# Adafruit_SIM808_Breakout.net
KiCad netlist of a schematic drawn in EAGLE
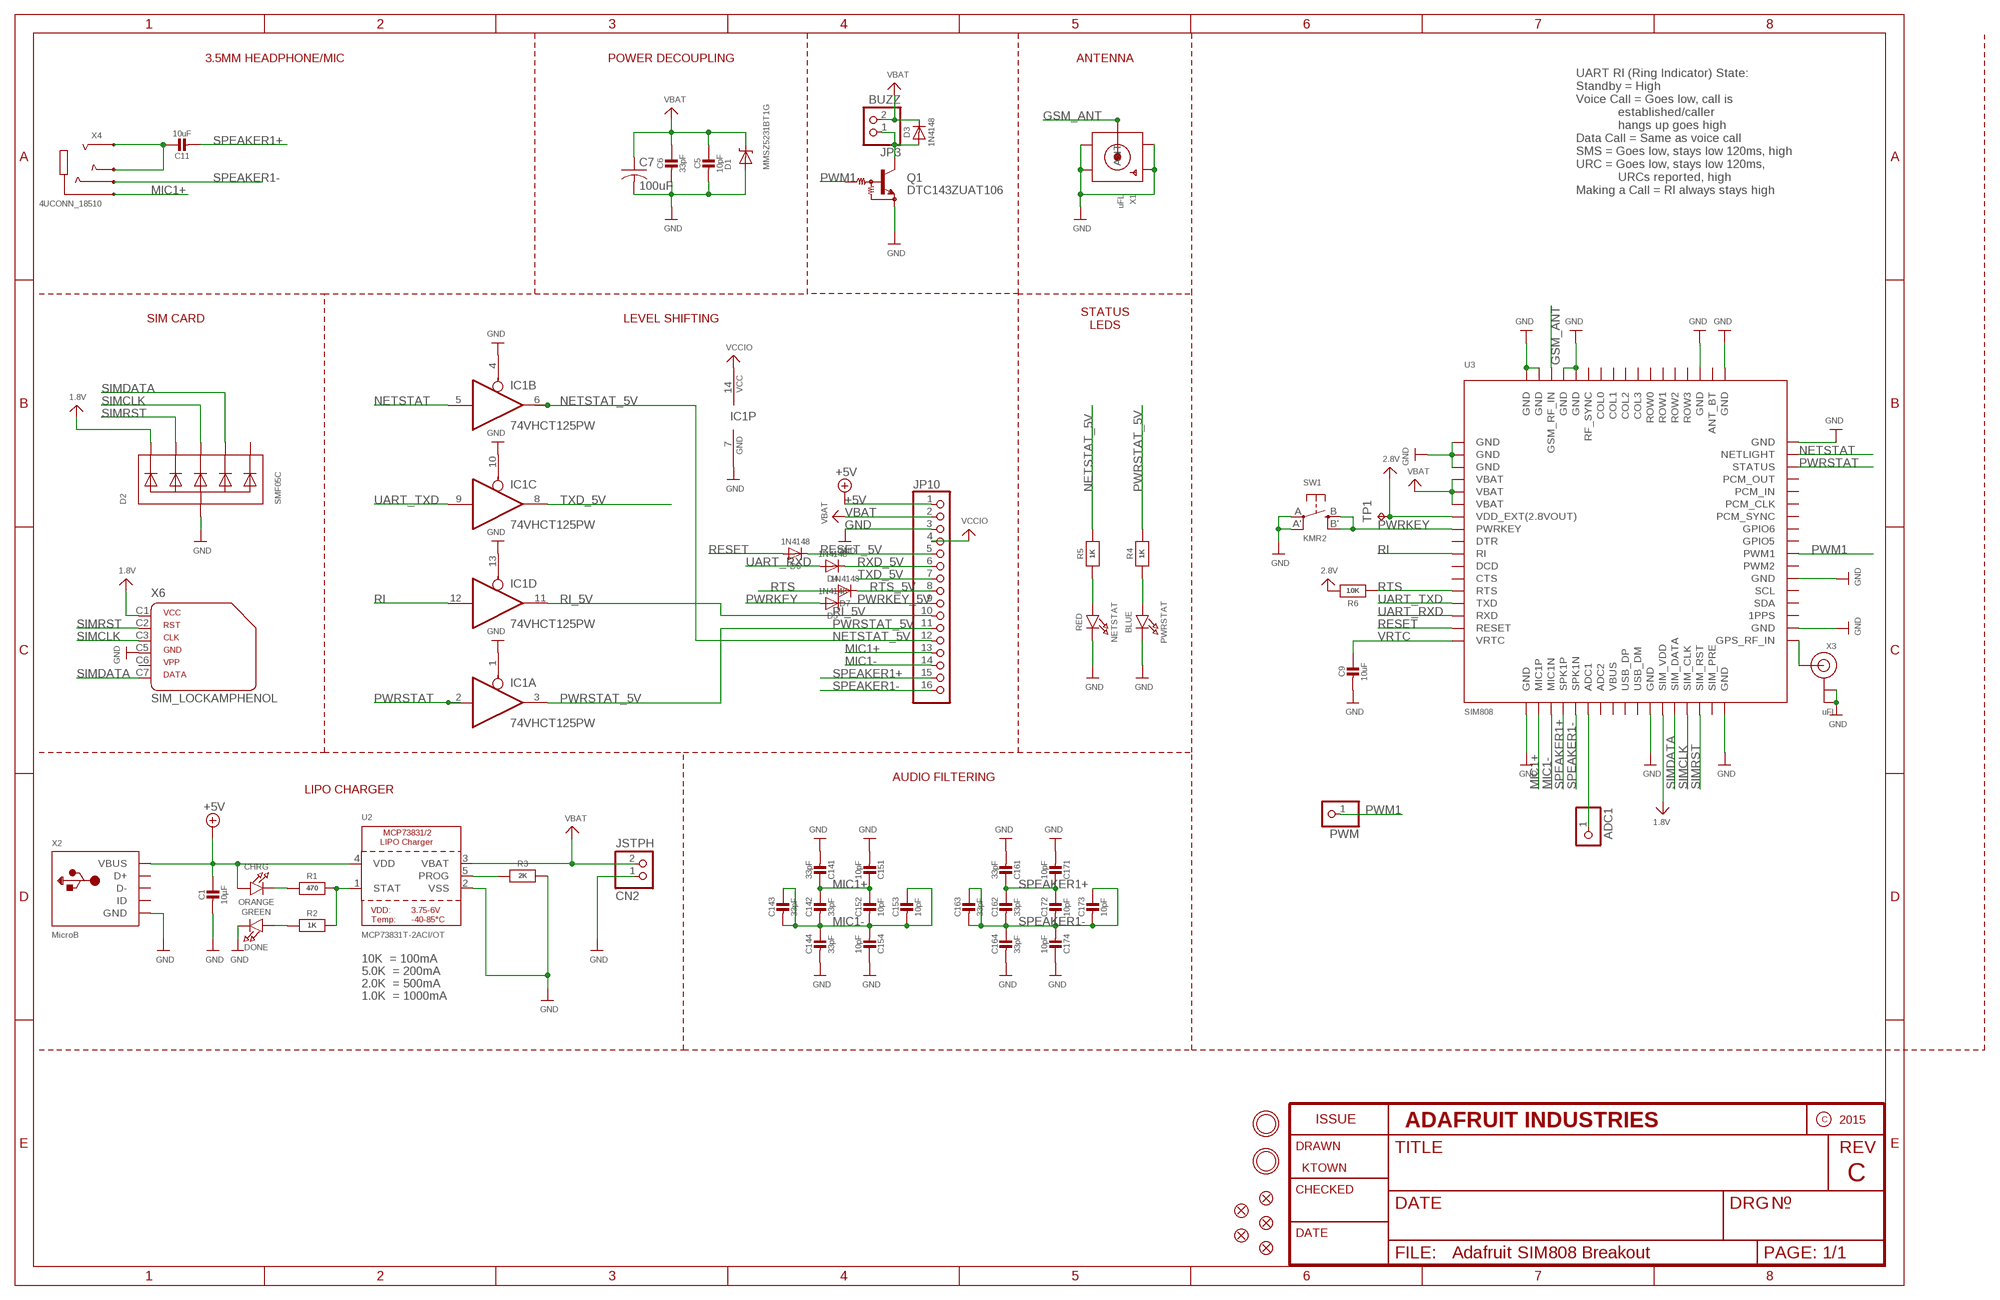
[diagram p0: schematic, sheet 1]

(export (version "E")
  (design (tool "Eeschema 10.0.6"))
  (components
    (comp (ref "ADC1")
      (value "PINHD-1X1CB")
      (footprint "eagle-import:1X01-CLEANBIG")
      (libsource (lib "eagle-import") (part "PINHD-1X1CB"))
    )
    (comp (ref "C1")
      (value "10µF")
      (footprint "eagle-import:0805-NO")
      (libsource (lib "eagle-import") (part "CAP_CERAMIC0805-NOOUTLINE"))
    )
    (comp (ref "C5")
      (value "10pF")
      (footprint "eagle-import:0805-NO")
      (libsource (lib "eagle-import") (part "CAP_CERAMIC0805-NOOUTLINE"))
    )
    (comp (ref "C6")
      (value "33pF")
      (footprint "eagle-import:0805-NO")
      (libsource (lib "eagle-import") (part "CAP_CERAMIC0805-NOOUTLINE"))
    )
    (comp (ref "C7")
      (value "100uF")
      (footprint "eagle-import:C1210")
      (libsource (lib "eagle-import") (part "C-USC1210"))
    )
    (comp (ref "C9")
      (value "10uF")
      (footprint "eagle-import:0805-NO")
      (libsource (lib "eagle-import") (part "CAP_CERAMIC0805-NOOUTLINE"))
    )
    (comp (ref "C11")
      (value "10uF")
      (footprint "eagle-import:0805-NO")
      (libsource (lib "eagle-import") (part "CAP_CERAMIC0805-NOOUTLINE"))
    )
    (comp (ref "C14")
      (value "33pF")
      (footprint "eagle-import:RESPACK_4X0603")
      (libsource (lib "eagle-import") (part "CAP_4PACK1206"))
    )
    (comp (ref "C15")
      (value "10pF")
      (footprint "eagle-import:RESPACK_4X0603")
      (libsource (lib "eagle-import") (part "CAP_4PACK1206"))
    )
    (comp (ref "C16")
      (value "33pF")
      (footprint "eagle-import:RESPACK_4X0603")
      (libsource (lib "eagle-import") (part "CAP_4PACK1206"))
    )
    (comp (ref "C17")
      (value "10pF")
      (footprint "eagle-import:RESPACK_4X0603")
      (libsource (lib "eagle-import") (part "CAP_4PACK1206"))
    )
    (comp (ref "CHRG")
      (value "ORANGE")
      (footprint "eagle-import:CHIPLED_0805_NOOUTLINE")
      (libsource (lib "eagle-import") (part "LED0805_NOOUTLINE"))
    )
    (comp (ref "CN2")
      (value "JSTPH")
      (footprint "eagle-import:JSTPH2")
      (libsource (lib "eagle-import") (part "JST_2PIN"))
    )
    (comp (ref "D1")
      (value "MMSZ5231BT1G")
      (footprint "eagle-import:SOD-123")
      (libsource (lib "eagle-import") (part "DIODE-ZENERSOD123"))
    )
    (comp (ref "D2")
      (value "SMF05C")
      (footprint "eagle-import:SOT363")
      (libsource (lib "eagle-import") (part "TVSARRAY_5LANE"))
    )
    (comp (ref "D3")
      (value "1N4148")
      (footprint "eagle-import:SOD-323")
      (libsource (lib "eagle-import") (part "DIODESOD-323"))
    )
    (comp (ref "D4")
      (value "1N4148")
      (footprint "eagle-import:SOD-323")
      (libsource (lib "eagle-import") (part "DIODESOD-323"))
    )
    (comp (ref "D5")
      (value "1N4148")
      (footprint "eagle-import:SOD-323")
      (libsource (lib "eagle-import") (part "DIODESOD-323"))
    )
    (comp (ref "D6")
      (value "1N4148")
      (footprint "eagle-import:SOD-323")
      (libsource (lib "eagle-import") (part "DIODESOD-323"))
    )
    (comp (ref "D7")
      (value "1N4148")
      (footprint "eagle-import:SOD-323")
      (libsource (lib "eagle-import") (part "DIODESOD-323"))
    )
    (comp (ref "DONE")
      (value "GREEN")
      (footprint "eagle-import:CHIPLED_0805_NOOUTLINE")
      (libsource (lib "eagle-import") (part "LED0805_NOOUTLINE"))
    )
    (comp (ref "FID1")
      (value "FIDUCIAL\"\"")
      (footprint "eagle-import:FIDUCIAL_1MM")
      (libsource (lib "eagle-import") (part "FIDUCIAL{dblquote}{dblquote}"))
    )
    (comp (ref "FID2")
      (value "FIDUCIAL\"\"")
      (footprint "eagle-import:FIDUCIAL_1MM")
      (libsource (lib "eagle-import") (part "FIDUCIAL{dblquote}{dblquote}"))
    )
    (comp (ref "FID3")
      (value "FIDUCIAL\"\"")
      (footprint "eagle-import:FIDUCIAL_1MM")
      (libsource (lib "eagle-import") (part "FIDUCIAL{dblquote}{dblquote}"))
    )
    (comp (ref "FID4")
      (value "FIDUCIAL\"\"")
      (footprint "eagle-import:FIDUCIAL_1MM")
      (libsource (lib "eagle-import") (part "FIDUCIAL{dblquote}{dblquote}"))
    )
    (comp (ref "FID5")
      (value "FIDUCIAL\"\"")
      (footprint "eagle-import:FIDUCIAL_1MM")
      (libsource (lib "eagle-import") (part "FIDUCIAL{dblquote}{dblquote}"))
    )
    (comp (ref "IC1")
      (value "74VHCT125PW")
      (footprint "eagle-import:TSSOP14")
      (libsource (lib "eagle-import") (part "74125PWABT"))
    )
    (comp (ref "JP3")
      (value "BUZZ")
      (footprint "eagle-import:1X02_ROUND")
      (libsource (lib "eagle-import") (part "HEADER-1X2ROUND"))
    )
    (comp (ref "JP10")
      (value "HEADER-1X16ROUND")
      (footprint "eagle-import:1X16_ROUND")
      (libsource (lib "eagle-import") (part "HEADER-1X16ROUND"))
    )
    (comp (ref "NETSTAT")
      (value "RED")
      (footprint "eagle-import:CHIPLED_0805_NOOUTLINE")
      (libsource (lib "eagle-import") (part "LED0805_NOOUTLINE"))
    )
    (comp (ref "PWM")
      (value "PINHD-1X1CB")
      (footprint "eagle-import:1X01-CLEANBIG")
      (libsource (lib "eagle-import") (part "PINHD-1X1CB"))
    )
    (comp (ref "PWRSTAT")
      (value "BLUE")
      (footprint "eagle-import:CHIPLED_0805_NOOUTLINE")
      (libsource (lib "eagle-import") (part "LED0805_NOOUTLINE"))
    )
    (comp (ref "Q1")
      (value "DTC143ZUAT106")
      (footprint "eagle-import:SC59-BEC")
      (libsource (lib "eagle-import") (part "-NPN_DRIVER-SC59-BECMUN2211T1"))
    )
    (comp (ref "R1")
      (value "470")
      (footprint "eagle-import:0805-NO")
      (libsource (lib "eagle-import") (part "RESISTOR0805_NOOUTLINE"))
    )
    (comp (ref "R2")
      (value "1K")
      (footprint "eagle-import:0805-NO")
      (libsource (lib "eagle-import") (part "RESISTOR0805_NOOUTLINE"))
    )
    (comp (ref "R3")
      (value "2K")
      (footprint "eagle-import:0805-NO")
      (libsource (lib "eagle-import") (part "RESISTOR0805_NOOUTLINE"))
    )
    (comp (ref "R4")
      (value "1K")
      (footprint "eagle-import:0805-NO")
      (libsource (lib "eagle-import") (part "RESISTOR0805_NOOUTLINE"))
    )
    (comp (ref "R5")
      (value "1K")
      (footprint "eagle-import:0805-NO")
      (libsource (lib "eagle-import") (part "RESISTOR0805_NOOUTLINE"))
    )
    (comp (ref "R6")
      (value "10K")
      (footprint "eagle-import:0805-NO")
      (libsource (lib "eagle-import") (part "RESISTOR0805_NOOUTLINE"))
    )
    (comp (ref "SW1")
      (value "KMR2")
      (footprint "eagle-import:BTN_KMR2_4.6X2.8")
      (libsource (lib "eagle-import") (part "SWITCH_TACT_SMT4.6X2.8"))
    )
    (comp (ref "TP1")
      (value "TPTP11R")
      (footprint "eagle-import:TP11R")
      (libsource (lib "eagle-import") (part "TPTP11R"))
    )
    (comp (ref "U$33")
      (value "MOUNTINGHOLE2.5")
      (footprint "eagle-import:MOUNTINGHOLE_2.5_PLATED")
      (libsource (lib "eagle-import") (part "MOUNTINGHOLE2.5"))
    )
    (comp (ref "U$34")
      (value "MOUNTINGHOLE2.5")
      (footprint "eagle-import:MOUNTINGHOLE_2.5_PLATED")
      (libsource (lib "eagle-import") (part "MOUNTINGHOLE2.5"))
    )
    (comp (ref "U2")
      (value "MCP73831T-2ACI/OT")
      (footprint "eagle-import:SOT23-5")
      (libsource (lib "eagle-import") (part "MCP73831/2"))
    )
    (comp (ref "U3")
      (value "SIM808")
      (footprint "eagle-import:SIM900_SMT")
      (libsource (lib "eagle-import") (part "GSM_SIM808_LITERAL"))
    )
    (comp (ref "X1")
      (value "uFL")
      (footprint "eagle-import:SMA_EDGELAUNCH_UFL")
      (libsource (lib "eagle-import") (part "SMACONNECTOR_EDGE_UFL"))
    )
    (comp (ref "X2")
      (value "MicroB")
      (footprint "eagle-import:4UCONN_20329")
      (libsource (lib "eagle-import") (part "USBMICRO_20329"))
    )
    (comp (ref "X3")
      (value "uFL")
      (footprint "eagle-import:U.FL")
      (libsource (lib "eagle-import") (part "ANTENNA_U.FL"))
    )
    (comp (ref "X4")
      (value "4UCONN_18510")
      (footprint "eagle-import:4UCONN_18510")
      (libsource (lib "eagle-import") (part "AUDIO_3.5MMJACK_4POL"))
    )
    (comp (ref "X6")
      (value "SIM_LOCKAMPHENOL")
      (footprint "eagle-import:C707_10M006_512_2")
      (libsource (lib "eagle-import") (part "SIM_LOCKAMPHENOL"))
    )
  )
  (nets
    (net (code "1") (name "+5V") (class "Default")
      (node (ref "C1") (pin "1") (pinfunction "1_1") (pintype "passive"))
      (node (ref "CHRG") (pin "A") (pinfunction "A_A") (pintype "passive"))
      (node (ref "JP10") (pin "1") (pinfunction "1_1") (pintype "passive"))
      (node (ref "U2") (pin "4") (pinfunction "VDD_4") (pintype "power_in"))
      (node (ref "X2") (pin "VBUS") (pinfunction "VBUS_VBUS") (pintype "power_in"))
    )
    (net (code "2") (name "/GSM_ANT") (class "Default")
      (node (ref "U3") (pin "P$66") (pinfunction "GSM_RF_IN_P$66") (pintype "input"))
      (node (ref "X1") (pin "P") (pinfunction "ANT_P") (pintype "bidirectional"))
    )
    (net (code "3") (name "/MIC1+") (class "Default")
      (node (ref "C14") (pin "1") (pinfunction "1_1") (pintype "passive"))
      (node (ref "C14") (pin "2") (pinfunction "1_2") (pintype "passive"))
      (node (ref "C15") (pin "1") (pinfunction "1_1") (pintype "passive"))
      (node (ref "C15") (pin "2") (pinfunction "1_2") (pintype "passive"))
      (node (ref "JP10") (pin "13") (pinfunction "13_13") (pintype "passive"))
      (node (ref "U3") (pin "P$19") (pinfunction "MIC1P_P$19") (pintype "input"))
      (node (ref "X4") (pin "1-GND") (pinfunction "TIP_1-GND") (pintype "passive"))
    )
    (net (code "4") (name "/MIC1-") (class "Default")
      (node (ref "C14") (pin "3") (pinfunction "1_3") (pintype "passive"))
      (node (ref "C14") (pin "4") (pinfunction "1_4") (pintype "passive"))
      (node (ref "C14") (pin "6") (pinfunction "2_6") (pintype "passive"))
      (node (ref "C14") (pin "7") (pinfunction "2_7") (pintype "passive"))
      (node (ref "C15") (pin "3") (pinfunction "1_3") (pintype "passive"))
      (node (ref "C15") (pin "5") (pinfunction "2_5") (pintype "passive"))
      (node (ref "C15") (pin "6") (pinfunction "2_6") (pintype "passive"))
      (node (ref "C15") (pin "7") (pinfunction "2_7") (pintype "passive"))
      (node (ref "JP10") (pin "14") (pinfunction "14_14") (pintype "passive"))
      (node (ref "U3") (pin "P$20") (pinfunction "MIC1N_P$20") (pintype "input"))
    )
    (net (code "5") (name "/NETSTAT") (class "Default")
      (node (ref "IC1") (pin "5") (pinfunction "I_5") (pintype "input"))
      (node (ref "U3") (pin "P$50") (pinfunction "NETLIGHT_P$50") (pintype "output"))
    )
    (net (code "6") (name "/NETSTAT_5V") (class "Default")
      (node (ref "IC1") (pin "6") (pinfunction "O_6") (pintype "tri_state"))
      (node (ref "JP10") (pin "12") (pinfunction "12_12") (pintype "passive"))
      (node (ref "R5") (pin "2") (pinfunction "2_2") (pintype "passive"))
    )
    (net (code "7") (name "/PWM1") (class "Default")
      (node (ref "PWM") (pin "1") (pinfunction "1_1") (pintype "passive"))
      (node (ref "Q1") (pin "B") (pinfunction "B_B") (pintype "passive"))
      (node (ref "U3") (pin "P$42") (pinfunction "PWM1_P$42") (pintype "output"))
    )
    (net (code "8") (name "/PWRKEY") (class "Default")
      (node (ref "D5") (pin "A") (pinfunction "A_A") (pintype "passive"))
      (node (ref "SW1") (pin "B") (pinfunction "S_B") (pintype "passive"))
      (node (ref "SW1") (pin "B'") (pinfunction "S1_B'") (pintype "passive"))
      (node (ref "U3") (pin "P$8") (pinfunction "PWRKEY_P$8") (pintype "input"))
    )
    (net (code "9") (name "/PWRKEY_5V") (class "Default")
      (node (ref "D5") (pin "C") (pinfunction "C_C") (pintype "passive"))
      (node (ref "JP10") (pin "9") (pinfunction "9_9") (pintype "passive"))
    )
    (net (code "10") (name "/PWRSTAT") (class "Default")
      (node (ref "IC1") (pin "2") (pinfunction "I_2") (pintype "input"))
      (node (ref "U3") (pin "P$49") (pinfunction "STATUS_P$49") (pintype "output"))
    )
    (net (code "11") (name "/PWRSTAT_5V") (class "Default")
      (node (ref "IC1") (pin "3") (pinfunction "O_3") (pintype "tri_state"))
      (node (ref "JP10") (pin "11") (pinfunction "11_11") (pintype "passive"))
      (node (ref "R4") (pin "2") (pinfunction "2_2") (pintype "passive"))
    )
    (net (code "12") (name "/RESET") (class "Default")
      (node (ref "D6") (pin "A") (pinfunction "A_A") (pintype "passive"))
      (node (ref "U3") (pin "P$16") (pinfunction "RESET_P$16") (pintype "input"))
    )
    (net (code "13") (name "/RESET_5V") (class "Default")
      (node (ref "D6") (pin "C") (pinfunction "C_C") (pintype "passive"))
      (node (ref "JP10") (pin "5") (pinfunction "5_5") (pintype "passive"))
    )
    (net (code "14") (name "/RI") (class "Default")
      (node (ref "IC1") (pin "12") (pinfunction "I_12") (pintype "input"))
      (node (ref "U3") (pin "P$10") (pinfunction "RI_P$10") (pintype "output"))
    )
    (net (code "15") (name "/RI_5V") (class "Default")
      (node (ref "IC1") (pin "11") (pinfunction "O_11") (pintype "tri_state"))
      (node (ref "JP10") (pin "10") (pinfunction "10_10") (pintype "passive"))
    )
    (net (code "16") (name "/RTS") (class "Default")
      (node (ref "D7") (pin "A") (pinfunction "A_A") (pintype "passive"))
      (node (ref "R6") (pin "1") (pinfunction "1_1") (pintype "passive"))
      (node (ref "U3") (pin "P$13") (pinfunction "RTS_P$13") (pintype "input"))
    )
    (net (code "17") (name "/RTS_5V") (class "Default")
      (node (ref "D7") (pin "C") (pinfunction "C_C") (pintype "passive"))
      (node (ref "JP10") (pin "8") (pinfunction "8_8") (pintype "passive"))
    )
    (net (code "18") (name "/RXD_5V") (class "Default")
      (node (ref "D4") (pin "C") (pinfunction "C_C") (pintype "passive"))
      (node (ref "JP10") (pin "6") (pinfunction "6_6") (pintype "passive"))
    )
    (net (code "19") (name "/SIMCLK") (class "Default")
      (node (ref "D2") (pin "4") (pinfunction "C3_4") (pintype "passive"))
      (node (ref "U3") (pin "P$31") (pinfunction "SIM_CLK_P$31") (pintype "output"))
      (node (ref "X6") (pin "C3") (pinfunction "3_C3") (pintype "passive"))
    )
    (net (code "20") (name "/SIMDATA") (class "Default")
      (node (ref "D2") (pin "5") (pinfunction "C4_5") (pintype "passive"))
      (node (ref "U3") (pin "P$30") (pinfunction "SIM_DATA_P$30") (pintype "bidirectional"))
      (node (ref "X6") (pin "C7") (pinfunction "6_C7") (pintype "passive"))
    )
    (net (code "21") (name "/SIMRST") (class "Default")
      (node (ref "D2") (pin "3") (pinfunction "C2_3") (pintype "passive"))
      (node (ref "U3") (pin "P$32") (pinfunction "SIM_RST_P$32") (pintype "output"))
      (node (ref "X6") (pin "C2") (pinfunction "2_C2") (pintype "passive"))
    )
    (net (code "22") (name "/SPEAKER1+") (class "Default")
      (node (ref "C11") (pin "2") (pinfunction "2_2") (pintype "passive"))
      (node (ref "C16") (pin "1") (pinfunction "1_1") (pintype "passive"))
      (node (ref "C16") (pin "2") (pinfunction "1_2") (pintype "passive"))
      (node (ref "C17") (pin "1") (pinfunction "1_1") (pintype "passive"))
      (node (ref "C17") (pin "2") (pinfunction "1_2") (pintype "passive"))
      (node (ref "JP10") (pin "15") (pinfunction "15_15") (pintype "passive"))
      (node (ref "U3") (pin "P$21") (pinfunction "SPK1P_P$21") (pintype "output"))
    )
    (net (code "23") (name "/SPEAKER1-") (class "Default")
      (node (ref "C16") (pin "3") (pinfunction "1_3") (pintype "passive"))
      (node (ref "C16") (pin "4") (pinfunction "1_4") (pintype "passive"))
      (node (ref "C16") (pin "6") (pinfunction "2_6") (pintype "passive"))
      (node (ref "C16") (pin "7") (pinfunction "2_7") (pintype "passive"))
      (node (ref "C17") (pin "3") (pinfunction "1_3") (pintype "passive"))
      (node (ref "C17") (pin "5") (pinfunction "2_5") (pintype "passive"))
      (node (ref "C17") (pin "6") (pinfunction "2_6") (pintype "passive"))
      (node (ref "C17") (pin "7") (pinfunction "2_7") (pintype "passive"))
      (node (ref "JP10") (pin "16") (pinfunction "16_16") (pintype "passive"))
      (node (ref "U3") (pin "P$22") (pinfunction "SPK1N_P$22") (pintype "output"))
      (node (ref "X4") (pin "4-INNER_SLEEVE") (pinfunction "RING1_4-INNER_SLEEVE") (pintype "passive"))
    )
    (net (code "24") (name "/TXD_5V") (class "Default")
      (node (ref "IC1") (pin "8") (pinfunction "O_8") (pintype "tri_state"))
      (node (ref "JP10") (pin "7") (pinfunction "7_7") (pintype "passive"))
    )
    (net (code "25") (name "/UART_RXD") (class "Default")
      (node (ref "D4") (pin "A") (pinfunction "A_A") (pintype "passive"))
      (node (ref "U3") (pin "P$15") (pinfunction "RXD_P$15") (pintype "input"))
    )
    (net (code "26") (name "/UART_TXD") (class "Default")
      (node (ref "IC1") (pin "9") (pinfunction "I_9") (pintype "input"))
      (node (ref "U3") (pin "P$14") (pinfunction "TXD_P$14") (pintype "output"))
    )
    (net (code "27") (name "/VBUS") (class "Default")
      (node (ref "U3") (pin "P$25") (pinfunction "VBUS_P$25") (pintype "power_in"))
    )
    (net (code "28") (name "/VRTC") (class "Default")
      (node (ref "C9") (pin "1") (pinfunction "1_1") (pintype "passive"))
      (node (ref "U3") (pin "P$17") (pinfunction "VRTC_P$17") (pintype "power_in"))
    )
    (net (code "29") (name "1.8V") (class "Default")
      (node (ref "D2") (pin "1") (pinfunction "C1_1") (pintype "passive"))
      (node (ref "U3") (pin "P$29") (pinfunction "SIM_VDD_P$29") (pintype "power_in"))
      (node (ref "X6") (pin "C1") (pinfunction "1_C1") (pintype "passive"))
    )
    (net (code "30") (name "2.8V") (class "Default")
      (node (ref "R6") (pin "2") (pinfunction "2_2") (pintype "passive"))
      (node (ref "TP1") (pin "TP") (pinfunction "TP_TP") (pintype "input"))
      (node (ref "U3") (pin "P$7") (pinfunction "VDD_EXT(2.8VOUT)_P$7") (pintype "power_in"))
    )
    (net (code "31") (name "GND") (class "Default")
      (node (ref "C1") (pin "2") (pinfunction "2_2") (pintype "passive"))
      (node (ref "C14") (pin "5") (pinfunction "2_5") (pintype "passive"))
      (node (ref "C14") (pin "8") (pinfunction "2_8") (pintype "passive"))
      (node (ref "C15") (pin "4") (pinfunction "1_4") (pintype "passive"))
      (node (ref "C15") (pin "8") (pinfunction "2_8") (pintype "passive"))
      (node (ref "C16") (pin "5") (pinfunction "2_5") (pintype "passive"))
      (node (ref "C16") (pin "8") (pinfunction "2_8") (pintype "passive"))
      (node (ref "C17") (pin "4") (pinfunction "1_4") (pintype "passive"))
      (node (ref "C17") (pin "8") (pinfunction "2_8") (pintype "passive"))
      (node (ref "C5") (pin "2") (pinfunction "2_2") (pintype "passive"))
      (node (ref "C6") (pin "2") (pinfunction "2_2") (pintype "passive"))
      (node (ref "C7") (pin "2") (pinfunction "2_2") (pintype "passive"))
      (node (ref "C9") (pin "2") (pinfunction "2_2") (pintype "passive"))
      (node (ref "CN2") (pin "1") (pinfunction "1_1") (pintype "passive"))
      (node (ref "D1") (pin "A") (pinfunction "A_A") (pintype "passive"))
      (node (ref "D2") (pin "2") (pinfunction "A_2") (pintype "passive"))
      (node (ref "DONE") (pin "C") (pinfunction "C_C") (pintype "passive"))
      (node (ref "IC1") (pin "1") (pinfunction "OE_1") (pintype "input"))
      (node (ref "IC1") (pin "10") (pinfunction "OE_10") (pintype "input"))
      (node (ref "IC1") (pin "13") (pinfunction "OE_13") (pintype "input"))
      (node (ref "IC1") (pin "4") (pinfunction "OE_4") (pintype "input"))
      (node (ref "IC1") (pin "7") (pinfunction "GND_7") (pintype "power_in"))
      (node (ref "JP10") (pin "3") (pinfunction "3_3") (pintype "passive"))
      (node (ref "NETSTAT") (pin "C") (pinfunction "C_C") (pintype "passive"))
      (node (ref "PWRSTAT") (pin "C") (pinfunction "C_C") (pintype "passive"))
      (node (ref "Q1") (pin "E") (pinfunction "E_E") (pintype "passive"))
      (node (ref "R3") (pin "2") (pinfunction "2_2") (pintype "passive"))
      (node (ref "SW1") (pin "A") (pinfunction "P_A") (pintype "passive"))
      (node (ref "SW1") (pin "A'") (pinfunction "P1_A'") (pintype "passive"))
      (node (ref "U2") (pin "2") (pinfunction "VSS_2") (pintype "power_in"))
      (node (ref "U3") (pin "P$1") (pinfunction "GND_P$1") (pintype "power_in"))
      (node (ref "U3") (pin "P$18") (pinfunction "GND_P$18") (pintype "power_in"))
      (node (ref "U3") (pin "P$2") (pinfunction "GND_P$2") (pintype "power_in"))
      (node (ref "U3") (pin "P$28") (pinfunction "GND_P$28") (pintype "power_in"))
      (node (ref "U3") (pin "P$3") (pinfunction "GND_P$3") (pintype "power_in"))
      (node (ref "U3") (pin "P$34") (pinfunction "GND_P$34") (pintype "power_in"))
      (node (ref "U3") (pin "P$36") (pinfunction "GND_P$36") (pintype "power_in"))
      (node (ref "U3") (pin "P$40") (pinfunction "GND_P$40") (pintype "power_in"))
      (node (ref "U3") (pin "P$51") (pinfunction "GND_P$51") (pintype "power_in"))
      (node (ref "U3") (pin "P$52") (pinfunction "GND_P$52") (pintype "power_in"))
      (node (ref "U3") (pin "P$54") (pinfunction "GND_P$54") (pintype "power_in"))
      (node (ref "U3") (pin "P$64") (pinfunction "GND_P$64") (pintype "power_in"))
      (node (ref "U3") (pin "P$65") (pinfunction "GND_P$65") (pintype "power_in"))
      (node (ref "U3") (pin "P$67") (pinfunction "GND_P$67") (pintype "power_in"))
      (node (ref "U3") (pin "P$68") (pinfunction "GND_P$68") (pintype "power_in"))
      (node (ref "X1") (pin "GND@1") (pinfunction "GND1_GND@1") (pintype "power_in"))
      (node (ref "X1") (pin "GND@2") (pinfunction "GND2_GND@2") (pintype "power_in"))
      (node (ref "X1") (pin "GND@3") (pinfunction "GND3_GND@3") (pintype "power_in"))
      (node (ref "X1") (pin "GND@4") (pinfunction "GND4_GND@4") (pintype "power_in"))
      (node (ref "X2") (pin "BASE@1") (pinfunction "GND_BASE@1") (pintype "power_in"))
      (node (ref "X2") (pin "BASE@2") (pinfunction "GND_BASE@2") (pintype "power_in"))
      (node (ref "X2") (pin "GND") (pinfunction "GND_GND") (pintype "power_in"))
      (node (ref "X2") (pin "SPRT@1") (pinfunction "GND_SPRT@1") (pintype "power_in"))
      (node (ref "X2") (pin "SPRT@2") (pinfunction "GND_SPRT@2") (pintype "power_in"))
      (node (ref "X2") (pin "SPRT@3") (pinfunction "GND_SPRT@3") (pintype "power_in"))
      (node (ref "X2") (pin "SPRT@4") (pinfunction "GND_SPRT@4") (pintype "power_in"))
      (node (ref "X3") (pin "1") (pinfunction "GND_1") (pintype "passive"))
      (node (ref "X3") (pin "2") (pinfunction "GND_2") (pintype "passive"))
      (node (ref "X6") (pin "C5") (pinfunction "4_C5") (pintype "passive"))
    )
    (net (code "32") (name "Net-(CHRG-PadC)") (class "Default")
      (node (ref "CHRG") (pin "C") (pinfunction "C_C") (pintype "passive"))
      (node (ref "R1") (pin "1") (pinfunction "1_1") (pintype "passive"))
    )
    (net (code "33") (name "Net-(D3-PadA)") (class "Default")
      (node (ref "D3") (pin "A") (pinfunction "A_A") (pintype "passive"))
      (node (ref "JP3") (pin "1") (pinfunction "1_1") (pintype "passive"))
      (node (ref "Q1") (pin "C") (pinfunction "C_C") (pintype "passive"))
    )
    (net (code "34") (name "Net-(DONE-PadA)") (class "Default")
      (node (ref "DONE") (pin "A") (pinfunction "A_A") (pintype "passive"))
      (node (ref "R2") (pin "1") (pinfunction "1_1") (pintype "passive"))
    )
    (net (code "35") (name "Net-(NETSTAT-PadA)") (class "Default")
      (node (ref "NETSTAT") (pin "A") (pinfunction "A_A") (pintype "passive"))
      (node (ref "R5") (pin "1") (pinfunction "1_1") (pintype "passive"))
    )
    (net (code "36") (name "Net-(PWRSTAT-PadA)") (class "Default")
      (node (ref "PWRSTAT") (pin "A") (pinfunction "A_A") (pintype "passive"))
      (node (ref "R4") (pin "1") (pinfunction "1_1") (pintype "passive"))
    )
    (net (code "37") (name "Net-(U2-PROG)") (class "Default")
      (node (ref "R3") (pin "1") (pinfunction "1_1") (pintype "passive"))
      (node (ref "U2") (pin "5") (pinfunction "PROG_5") (pintype "input"))
    )
    (net (code "38") (name "Net-(U2-STAT)") (class "Default")
      (node (ref "R1") (pin "2") (pinfunction "2_2") (pintype "passive"))
      (node (ref "R2") (pin "2") (pinfunction "2_2") (pintype "passive"))
      (node (ref "U2") (pin "1") (pinfunction "STAT_1") (pintype "output"))
    )
    (net (code "39") (name "Net-(U3-ADC1)") (class "Default")
      (node (ref "ADC1") (pin "1") (pinfunction "1_1") (pintype "passive"))
      (node (ref "U3") (pin "P$23") (pinfunction "ADC1_P$23") (pintype "input"))
    )
    (net (code "40") (name "Net-(U3-GPS_RF_IN)") (class "Default")
      (node (ref "U3") (pin "P$35") (pinfunction "GPS_RF_IN_P$35") (pintype "bidirectional"))
      (node (ref "X3") (pin "3") (pinfunction "SIGNAL_3") (pintype "passive"))
    )
    (net (code "41") (name "Net-(X4-RING2)") (class "Default")
      (node (ref "C11") (pin "1") (pinfunction "1_1") (pintype "passive"))
      (node (ref "X4") (pin "2-TIP") (pinfunction "RING3_2-TIP") (pintype "passive"))
      (node (ref "X4") (pin "3-OUTER_SLEEVE") (pinfunction "RING2_3-OUTER_SLEEVE") (pintype "passive"))
    )
    (net (code "42") (name "VBAT") (class "Default")
      (node (ref "C5") (pin "1") (pinfunction "1_1") (pintype "passive"))
      (node (ref "C6") (pin "1") (pinfunction "1_1") (pintype "passive"))
      (node (ref "C7") (pin "1") (pinfunction "1_1") (pintype "passive"))
      (node (ref "CN2") (pin "2") (pinfunction "2_2") (pintype "passive"))
      (node (ref "D1") (pin "C") (pinfunction "C_C") (pintype "passive"))
      (node (ref "D3") (pin "C") (pinfunction "C_C") (pintype "passive"))
      (node (ref "JP10") (pin "2") (pinfunction "2_2") (pintype "passive"))
      (node (ref "JP3") (pin "2") (pinfunction "2_2") (pintype "passive"))
      (node (ref "U2") (pin "3") (pinfunction "VBAT_3") (pintype "power_in"))
      (node (ref "U3") (pin "P$4") (pinfunction "VBAT_P$4") (pintype "power_in"))
      (node (ref "U3") (pin "P$5") (pinfunction "VBAT_P$5") (pintype "power_in"))
      (node (ref "U3") (pin "P$6") (pinfunction "VBAT_P$6") (pintype "power_in"))
    )
    (net (code "43") (name "VCCIO") (class "Default")
      (node (ref "IC1") (pin "14") (pinfunction "VCC_14") (pintype "power_in"))
      (node (ref "JP10") (pin "4") (pinfunction "4_4") (pintype "passive"))
    )
    (net (code "44") (name "unconnected-(D2-C5-Pad6)") (class "Default")
      (node (ref "D2") (pin "6") (pinfunction "C5_6") (pintype "passive"))
    )
    (net (code "45") (name "unconnected-(U3-1PPS-PadP$37)") (class "Default")
      (node (ref "U3") (pin "P$37") (pinfunction "1PPS_P$37") (pintype "input"))
    )
    (net (code "46") (name "unconnected-(U3-ADC2-PadP$24)") (class "Default")
      (node (ref "U3") (pin "P$24") (pinfunction "ADC2_P$24") (pintype "input"))
    )
    (net (code "47") (name "unconnected-(U3-ANT_BT-PadP$53)") (class "Default")
      (node (ref "U3") (pin "P$53") (pinfunction "ANT_BT_P$53") (pintype "bidirectional"))
    )
    (net (code "48") (name "unconnected-(U3-COL0-PadP$62)") (class "Default")
      (node (ref "U3") (pin "P$62") (pinfunction "COL0_P$62") (pintype "input"))
    )
    (net (code "49") (name "unconnected-(U3-COL1-PadP$61)") (class "Default")
      (node (ref "U3") (pin "P$61") (pinfunction "COL1_P$61") (pintype "input"))
    )
    (net (code "50") (name "unconnected-(U3-COL2-PadP$60)") (class "Default")
      (node (ref "U3") (pin "P$60") (pinfunction "COL2_P$60") (pintype "input"))
    )
    (net (code "51") (name "unconnected-(U3-COL3-PadP$59)") (class "Default")
      (node (ref "U3") (pin "P$59") (pinfunction "COL3_P$59") (pintype "input"))
    )
    (net (code "52") (name "unconnected-(U3-CTS-PadP$12)") (class "Default")
      (node (ref "U3") (pin "P$12") (pinfunction "CTS_P$12") (pintype "output"))
    )
    (net (code "53") (name "unconnected-(U3-DCD-PadP$11)") (class "Default")
      (node (ref "U3") (pin "P$11") (pinfunction "DCD_P$11") (pintype "output"))
    )
    (net (code "54") (name "unconnected-(U3-DTR-PadP$9)") (class "Default")
      (node (ref "U3") (pin "P$9") (pinfunction "DTR_P$9") (pintype "input"))
    )
    (net (code "55") (name "unconnected-(U3-GPIO5-PadP$43)") (class "Default")
      (node (ref "U3") (pin "P$43") (pinfunction "GPIO5_P$43") (pintype "bidirectional"))
    )
    (net (code "56") (name "unconnected-(U3-GPIO6-PadP$44)") (class "Default")
      (node (ref "U3") (pin "P$44") (pinfunction "GPIO6_P$44") (pintype "bidirectional"))
    )
    (net (code "57") (name "unconnected-(U3-PCM_CLK-PadP$46)") (class "Default")
      (node (ref "U3") (pin "P$46") (pinfunction "PCM_CLK_P$46") (pintype "input"))
    )
    (net (code "58") (name "unconnected-(U3-PCM_IN-PadP$47)") (class "Default")
      (node (ref "U3") (pin "P$47") (pinfunction "PCM_IN_P$47") (pintype "input"))
    )
    (net (code "59") (name "unconnected-(U3-PCM_OUT-PadP$48)") (class "Default")
      (node (ref "U3") (pin "P$48") (pinfunction "PCM_OUT_P$48") (pintype "output"))
    )
    (net (code "60") (name "unconnected-(U3-PCM_SYNC-PadP$45)") (class "Default")
      (node (ref "U3") (pin "P$45") (pinfunction "PCM_SYNC_P$45") (pintype "output"))
    )
    (net (code "61") (name "unconnected-(U3-PWM2-PadP$41)") (class "Default")
      (node (ref "U3") (pin "P$41") (pinfunction "PWM2_P$41") (pintype "output"))
    )
    (net (code "62") (name "unconnected-(U3-RF_SYNC-PadP$63)") (class "Default")
      (node (ref "U3") (pin "P$63") (pinfunction "RF_SYNC_P$63") (pintype "output"))
    )
    (net (code "63") (name "unconnected-(U3-ROW0-PadP$58)") (class "Default")
      (node (ref "U3") (pin "P$58") (pinfunction "ROW0_P$58") (pintype "output"))
    )
    (net (code "64") (name "unconnected-(U3-ROW1-PadP$57)") (class "Default")
      (node (ref "U3") (pin "P$57") (pinfunction "ROW1_P$57") (pintype "output"))
    )
    (net (code "65") (name "unconnected-(U3-ROW2-PadP$56)") (class "Default")
      (node (ref "U3") (pin "P$56") (pinfunction "ROW2_P$56") (pintype "output"))
    )
    (net (code "66") (name "unconnected-(U3-ROW3-PadP$55)") (class "Default")
      (node (ref "U3") (pin "P$55") (pinfunction "ROW3_P$55") (pintype "output"))
    )
    (net (code "67") (name "unconnected-(U3-SCL-PadP$39)") (class "Default")
      (node (ref "U3") (pin "P$39") (pinfunction "SCL_P$39") (pintype "output"))
    )
    (net (code "68") (name "unconnected-(U3-SDA-PadP$38)") (class "Default")
      (node (ref "U3") (pin "P$38") (pinfunction "SDA_P$38") (pintype "bidirectional"))
    )
    (net (code "69") (name "unconnected-(U3-SIM_PRE-PadP$33)") (class "Default")
      (node (ref "U3") (pin "P$33") (pinfunction "SIM_PRE_P$33") (pintype "input"))
    )
    (net (code "70") (name "unconnected-(U3-USB_DM-PadP$27)") (class "Default")
      (node (ref "U3") (pin "P$27") (pinfunction "USB_DM_P$27") (pintype "bidirectional"))
    )
    (net (code "71") (name "unconnected-(U3-USB_DP-PadP$26)") (class "Default")
      (node (ref "U3") (pin "P$26") (pinfunction "USB_DP_P$26") (pintype "bidirectional"))
    )
    (net (code "72") (name "unconnected-(X2-PadD+)") (class "Default")
      (node (ref "X2") (pin "D+") (pinfunction "D+_D+") (pintype "bidirectional"))
    )
    (net (code "73") (name "unconnected-(X2-PadD-)") (class "Default")
      (node (ref "X2") (pin "D-") (pinfunction "D-_D-") (pintype "bidirectional"))
    )
    (net (code "74") (name "unconnected-(X2-PadID)") (class "Default")
      (node (ref "X2") (pin "ID") (pinfunction "ID_ID") (pintype "bidirectional"))
    )
    (net (code "75") (name "unconnected-(X6-5-PadC6)") (class "Default")
      (node (ref "X6") (pin "C6") (pinfunction "5_C6") (pintype "passive"))
    )
  )
)
